# 03_POWER.net
KiCad netlist of a schematic drawn in Altium Designer
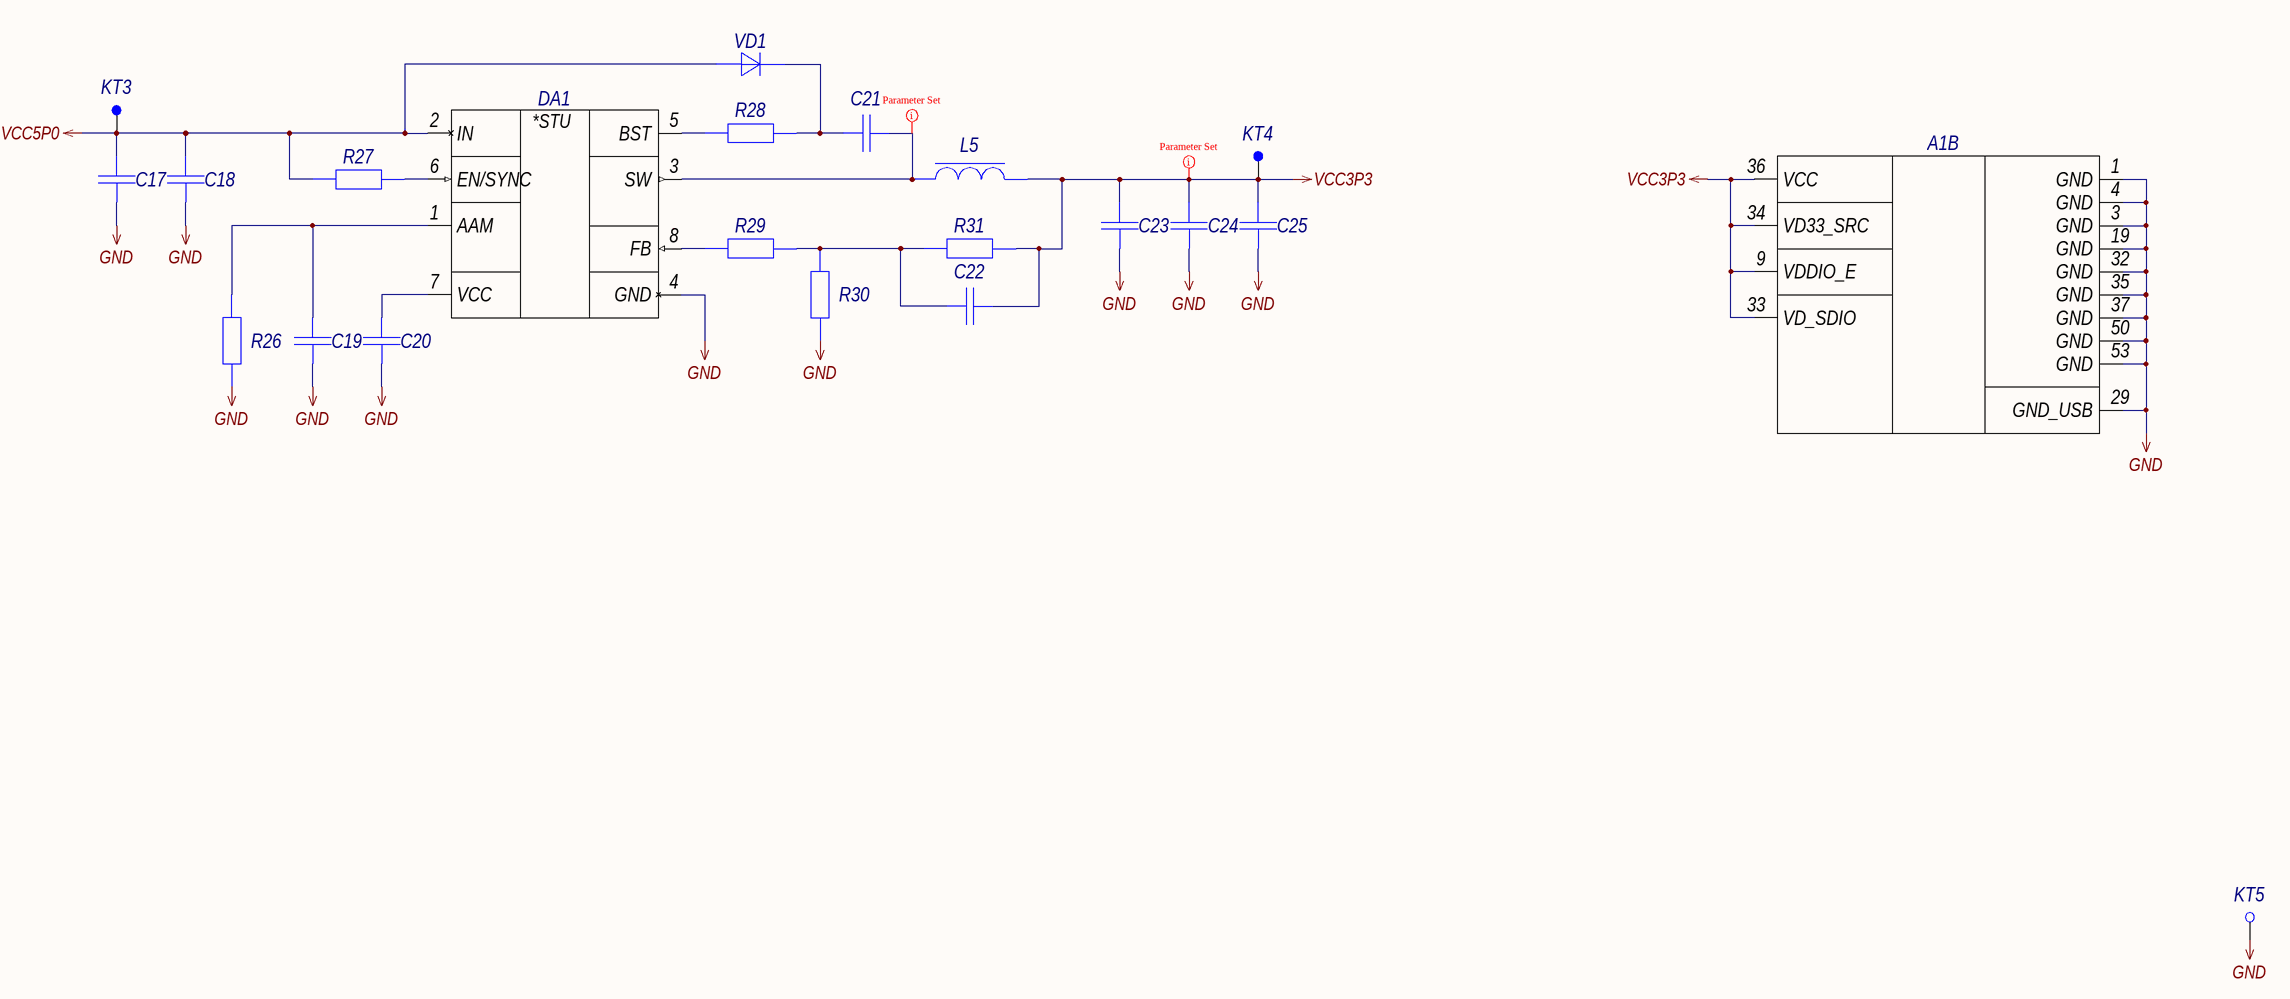
[diagram p0: 03_POWER.SchDoc]

(export (version "E")
  (design (tool "Eeschema 10.0.6"))
  (components
    (comp (ref "A1")
      (value "AMB-02")
      (footprint "AMB-02")
      (fields
        (field (name "PART NUMBER") "MJIOT-AMB-02")
        (field (name "MANUFACTURER") "MJIOT")
        (field (name "PUBLISHER") "Andrew Danich")
      )
      (libsource (lib "ADLib") (part "AMB-02"))
    )
    (comp (ref "C17")
      (value "Capacitor")
      (footprint "C0805_L")
      (fields
        (field (name "PART NUMBER") "GRM21BR60J226ME39L")
        (field (name "VOLTAGE") "6.3V")
        (field (name "TOLERANCE") "±20%")
        (field (name "PUBLISHER") "Andrew Danich")
      )
      (libsource (lib "ADLib") (part "Capacitor"))
    )
    (comp (ref "C18")
      (value "Capacitor")
      (footprint "C0603_L")
      (fields
        (field (name "PART NUMBER") "GRM188R72A104KA35D")
        (field (name "VOLTAGE") "100V")
        (field (name "TOLERANCE") "±10%")
        (field (name "PUBLISHER") "Andrew Danich")
      )
      (libsource (lib "ADLib") (part "Capacitor"))
    )
    (comp (ref "C19")
      (value "Capacitor")
      (footprint "C0603_L")
      (fields
        (field (name "PART NUMBER") "GRM1885C2A102JA01D")
        (field (name "VOLTAGE") "100V")
        (field (name "TOLERANCE") "±5%")
        (field (name "PUBLISHER") "Andrew Danich")
      )
      (libsource (lib "ADLib") (part "Capacitor"))
    )
    (comp (ref "C20")
      (value "Capacitor")
      (footprint "C0603_L")
      (fields
        (field (name "PART NUMBER") "GRM188R72A104KA35D")
        (field (name "VOLTAGE") "100V")
        (field (name "TOLERANCE") "±10%")
        (field (name "PUBLISHER") "Andrew Danich")
      )
      (libsource (lib "ADLib") (part "Capacitor"))
    )
    (comp (ref "C21")
      (value "Capacitor")
      (footprint "C0603_L")
      (fields
        (field (name "PART NUMBER") "GRM188R72A104KA35D")
        (field (name "VOLTAGE") "100V")
        (field (name "TOLERANCE") "±10%")
        (field (name "PUBLISHER") "Andrew Danich")
      )
      (libsource (lib "ADLib") (part "Capacitor"))
    )
    (comp (ref "C22")
      (value "Capacitor")
      (footprint "C0603_L")
      (fields
        (field (name "PART NUMBER") "GRM1885C1H330JA01D")
        (field (name "VOLTAGE") "50V")
        (field (name "TOLERANCE") "±5%")
        (field (name "PUBLISHER") "Andrew Danich")
      )
      (libsource (lib "ADLib") (part "Capacitor"))
    )
    (comp (ref "C23")
      (value "Capacitor")
      (footprint "C0805_L")
      (fields
        (field (name "PART NUMBER") "GRM21BR60J226ME39L")
        (field (name "VOLTAGE") "6.3V")
        (field (name "TOLERANCE") "±20%")
        (field (name "PUBLISHER") "Andrew Danich")
      )
      (libsource (lib "ADLib") (part "Capacitor"))
    )
    (comp (ref "C24")
      (value "Capacitor")
      (footprint "C0805_L")
      (fields
        (field (name "PART NUMBER") "GRM21BR60J226ME39L")
        (field (name "VOLTAGE") "6.3V")
        (field (name "TOLERANCE") "±20%")
        (field (name "PUBLISHER") "Andrew Danich")
      )
      (libsource (lib "ADLib") (part "Capacitor"))
    )
    (comp (ref "C25")
      (value "Capacitor")
      (footprint "C0805_L")
      (fields
        (field (name "PART NUMBER") "GRM21BR60J226ME39L")
        (field (name "VOLTAGE") "6.3V")
        (field (name "TOLERANCE") "±20%")
        (field (name "PUBLISHER") "Andrew Danich")
      )
      (libsource (lib "ADLib") (part "Capacitor"))
    )
    (comp (ref "DA1")
      (value "MP2315GJ")
      (footprint "TSOT-23-8_065P290X160X100_N")
      (fields
        (field (name "PART NUMBER") "MP2315GJ-Z")
        (field (name "MANUFACTURER") "Monolithic Power Systems")
        (field (name "PUBLISHER") "Andrew Danich")
      )
      (libsource (lib "ADLib") (part "MP2315GJ"))
    )
    (comp (ref "KT3")
      (value "+5V")
      (footprint "TP-SMT-C-0.8mm")
      (fields (field (name "PART NUMBER") "TestPoint-SMT") (field (name "PUBLISHER") "Andrew Danich"))
      (libsource (lib "ADLib") (part "TP-S-1"))
    )
    (comp (ref "KT4")
      (value "+3.3V")
      (footprint "TP-SMT-C-0.8mm")
      (fields (field (name "PART NUMBER") "TestPoint-SMT") (field (name "PUBLISHER") "Andrew Danich"))
      (libsource (lib "ADLib") (part "TP-S-1"))
    )
    (comp (ref "KT5")
      (value "GND")
      (footprint "5001")
      (fields
        (field (name "PART NUMBER") "5001")
        (field (name "MANUFACTURER") "Keystone Electronics")
        (field (name "PUBLISHER") "Andrew Danich")
      )
      (libsource (lib "ADLib") (part "TP-1"))
    )
    (comp (ref "L5")
      (value "Coil")
      (footprint "SRP4020TA-Series")
      (fields
        (field (name "PART NUMBER") "SRP4020TA-4R7M")
        (field (name "TOLERANCE") "±20%")
        (field (name "MANUFACTURER") "Bourns")
        (field (name "PUBLISHER") "Andrew Danich")
      )
      (libsource (lib "ADLib") (part "Coil"))
    )
    (comp (ref "R26")
      (value "Resistor")
      (footprint "R0603_L")
      (fields
        (field (name "PART NUMBER") "RC0603FR-0763K4L")
        (field (name "TOLERANCE") "±1%")
        (field (name "MANUFACTURER") "Yageo")
        (field (name "PUBLISHER") "Andrew Danich")
      )
      (libsource (lib "ADLib") (part "Resistor"))
    )
    (comp (ref "R27")
      (value "Resistor")
      (footprint "R0603_L")
      (fields
        (field (name "PART NUMBER") "RC0603JR-07100KL")
        (field (name "TOLERANCE") "±5%")
        (field (name "MANUFACTURER") "Yageo")
        (field (name "PUBLISHER") "Andrew Danich")
      )
      (libsource (lib "ADLib") (part "Resistor"))
    )
    (comp (ref "R28")
      (value "Resistor")
      (footprint "R0603_L")
      (fields
        (field (name "PART NUMBER") "RC0603JR-0720RL")
        (field (name "TOLERANCE") "±5%")
        (field (name "MANUFACTURER") "Yageo")
        (field (name "PUBLISHER") "Andrew Danich")
      )
      (libsource (lib "ADLib") (part "Resistor"))
    )
    (comp (ref "R29")
      (value "Resistor")
      (footprint "R0603_L")
      (fields
        (field (name "PART NUMBER") "RC0603JR-0733KL")
        (field (name "TOLERANCE") "±5%")
        (field (name "MANUFACTURER") "Yageo")
        (field (name "PUBLISHER") "Andrew Danich")
      )
      (libsource (lib "ADLib") (part "Resistor"))
    )
    (comp (ref "R30")
      (value "Resistor")
      (footprint "R0603_L")
      (fields
        (field (name "PART NUMBER") "RC0603FR-0712K7L")
        (field (name "TOLERANCE") "±1%")
        (field (name "MANUFACTURER") "Yageo")
        (field (name "PUBLISHER") "Andrew Danich")
      )
      (libsource (lib "ADLib") (part "Resistor"))
    )
    (comp (ref "R31")
      (value "Resistor")
      (footprint "R0603_L")
      (fields
        (field (name "PART NUMBER") "RC0603FR-0740K2L")
        (field (name "TOLERANCE") "±1%")
        (field (name "MANUFACTURER") "Yageo")
        (field (name "PUBLISHER") "Andrew Danich")
      )
      (libsource (lib "ADLib") (part "Resistor"))
    )
    (comp (ref "VD1")
      (value "Diode")
      (footprint "SOD-323")
      (fields
        (field (name "PART NUMBER") "1N4148WS-7-F")
        (field (name "MANUFACTURER") "Diodes Incorporated")
        (field (name "PUBLISHER") "Andrew Danich")
      )
      (libsource (lib "ADLib") (part "Diode"))
    )
  )
  (nets
    (net (code "1") (name "GND") (class "Default")
      (node (ref "A1") (pin "1") (pinfunction "GND_1") (pintype "power_in"))
      (node (ref "A1") (pin "19") (pinfunction "GND_19") (pintype "power_in"))
      (node (ref "A1") (pin "29") (pinfunction "GND_USB_29") (pintype "power_in"))
      (node (ref "A1") (pin "3") (pinfunction "GND_3") (pintype "power_in"))
      (node (ref "A1") (pin "32") (pinfunction "GND_32") (pintype "power_in"))
      (node (ref "A1") (pin "35") (pinfunction "GND_35") (pintype "power_in"))
      (node (ref "A1") (pin "37") (pinfunction "GND_37") (pintype "power_in"))
      (node (ref "A1") (pin "4") (pinfunction "GND_4") (pintype "power_in"))
      (node (ref "A1") (pin "50") (pinfunction "GND_50") (pintype "power_in"))
      (node (ref "A1") (pin "53") (pinfunction "GND_53") (pintype "power_in"))
      (node (ref "C17") (pin "1") (pinfunction "1_1") (pintype "passive"))
      (node (ref "C18") (pin "1") (pinfunction "1_1") (pintype "passive"))
      (node (ref "C19") (pin "1") (pinfunction "1_1") (pintype "passive"))
      (node (ref "C20") (pin "1") (pinfunction "1_1") (pintype "passive"))
      (node (ref "C23") (pin "1") (pinfunction "1_1") (pintype "passive"))
      (node (ref "C24") (pin "1") (pinfunction "1_1") (pintype "passive"))
      (node (ref "C25") (pin "1") (pinfunction "1_1") (pintype "passive"))
      (node (ref "DA1") (pin "4") (pinfunction "GND_4") (pintype "power_in"))
      (node (ref "KT5") (pin "1") (pinfunction "1_1") (pintype "passive"))
      (node (ref "R26") (pin "1") (pinfunction "1_1") (pintype "passive"))
      (node (ref "R30") (pin "1") (pinfunction "1_1") (pintype "passive"))
    )
    (net (code "2") (name "Net-(C22-Pad1)") (class "Default")
      (node (ref "C22") (pin "1") (pinfunction "1_1") (pintype "passive"))
      (node (ref "R29") (pin "2") (pinfunction "2_2") (pintype "passive"))
      (node (ref "R30") (pin "2") (pinfunction "2_2") (pintype "passive"))
      (node (ref "R31") (pin "1") (pinfunction "1_1") (pintype "passive"))
    )
    (net (code "3") (name "Net-(DA1-AAM)") (class "Default")
      (node (ref "C19") (pin "2") (pinfunction "2_2") (pintype "passive"))
      (node (ref "DA1") (pin "1") (pinfunction "AAM_1") (pintype "passive"))
      (node (ref "R26") (pin "2") (pinfunction "2_2") (pintype "passive"))
    )
    (net (code "4") (name "Net-(DA1-BST)") (class "Default")
      (node (ref "DA1") (pin "5") (pinfunction "BST_5") (pintype "passive"))
      (node (ref "R28") (pin "1") (pinfunction "1_1") (pintype "passive"))
    )
    (net (code "5") (name "Net-(DA1-EN{slash}SYNC)") (class "Default")
      (node (ref "DA1") (pin "6") (pinfunction "EN/SYNC_6") (pintype "input"))
      (node (ref "R27") (pin "2") (pinfunction "2_2") (pintype "passive"))
    )
    (net (code "6") (name "Net-(DA1-FB)") (class "Default")
      (node (ref "DA1") (pin "8") (pinfunction "FB_8") (pintype "input"))
      (node (ref "R29") (pin "1") (pinfunction "1_1") (pintype "passive"))
    )
    (net (code "7") (name "Net-(DA1-SW)") (class "Default")
      (node (ref "C21") (pin "2") (pinfunction "2_2") (pintype "passive"))
      (node (ref "DA1") (pin "3") (pinfunction "SW_3") (pintype "output"))
      (node (ref "L5") (pin "1") (pinfunction "1_1") (pintype "passive"))
    )
    (net (code "8") (name "Net-(DA1-VCC)") (class "Default")
      (node (ref "C20") (pin "2") (pinfunction "2_2") (pintype "passive"))
      (node (ref "DA1") (pin "7") (pinfunction "VCC_7") (pintype "power_in"))
    )
    (net (code "9") (name "Net-(VD1-К)") (class "Default")
      (node (ref "C21") (pin "1") (pinfunction "1_1") (pintype "passive"))
      (node (ref "R28") (pin "2") (pinfunction "2_2") (pintype "passive"))
      (node (ref "VD1") (pin "2") (pinfunction "К_2") (pintype "passive"))
    )
    (net (code "10") (name "VCC3P3") (class "Default")
      (node (ref "A1") (pin "33") (pinfunction "VD_SDIO_33") (pintype "power_in"))
      (node (ref "A1") (pin "34") (pinfunction "VD33_SRC_34") (pintype "power_in"))
      (node (ref "A1") (pin "36") (pinfunction "VCC_36") (pintype "power_in"))
      (node (ref "A1") (pin "9") (pinfunction "VDDIO_E_9") (pintype "power_in"))
      (node (ref "C22") (pin "2") (pinfunction "2_2") (pintype "passive"))
      (node (ref "C23") (pin "2") (pinfunction "2_2") (pintype "passive"))
      (node (ref "C24") (pin "2") (pinfunction "2_2") (pintype "passive"))
      (node (ref "C25") (pin "2") (pinfunction "2_2") (pintype "passive"))
      (node (ref "KT4") (pin "1") (pinfunction "1_1") (pintype "passive"))
      (node (ref "L5") (pin "2") (pinfunction "2_2") (pintype "passive"))
      (node (ref "R31") (pin "2") (pinfunction "2_2") (pintype "passive"))
    )
    (net (code "11") (name "VCC5P0") (class "Default")
      (node (ref "C17") (pin "2") (pinfunction "2_2") (pintype "passive"))
      (node (ref "C18") (pin "2") (pinfunction "2_2") (pintype "passive"))
      (node (ref "DA1") (pin "2") (pinfunction "IN_2") (pintype "power_in"))
      (node (ref "KT3") (pin "1") (pinfunction "1_1") (pintype "passive"))
      (node (ref "R27") (pin "1") (pinfunction "1_1") (pintype "passive"))
      (node (ref "VD1") (pin "1") (pinfunction "А_1") (pintype "passive"))
    )
  )
)
